# Adafruit_2_4in_TFT_Breakout.net
KiCad netlist of a schematic drawn in EAGLE
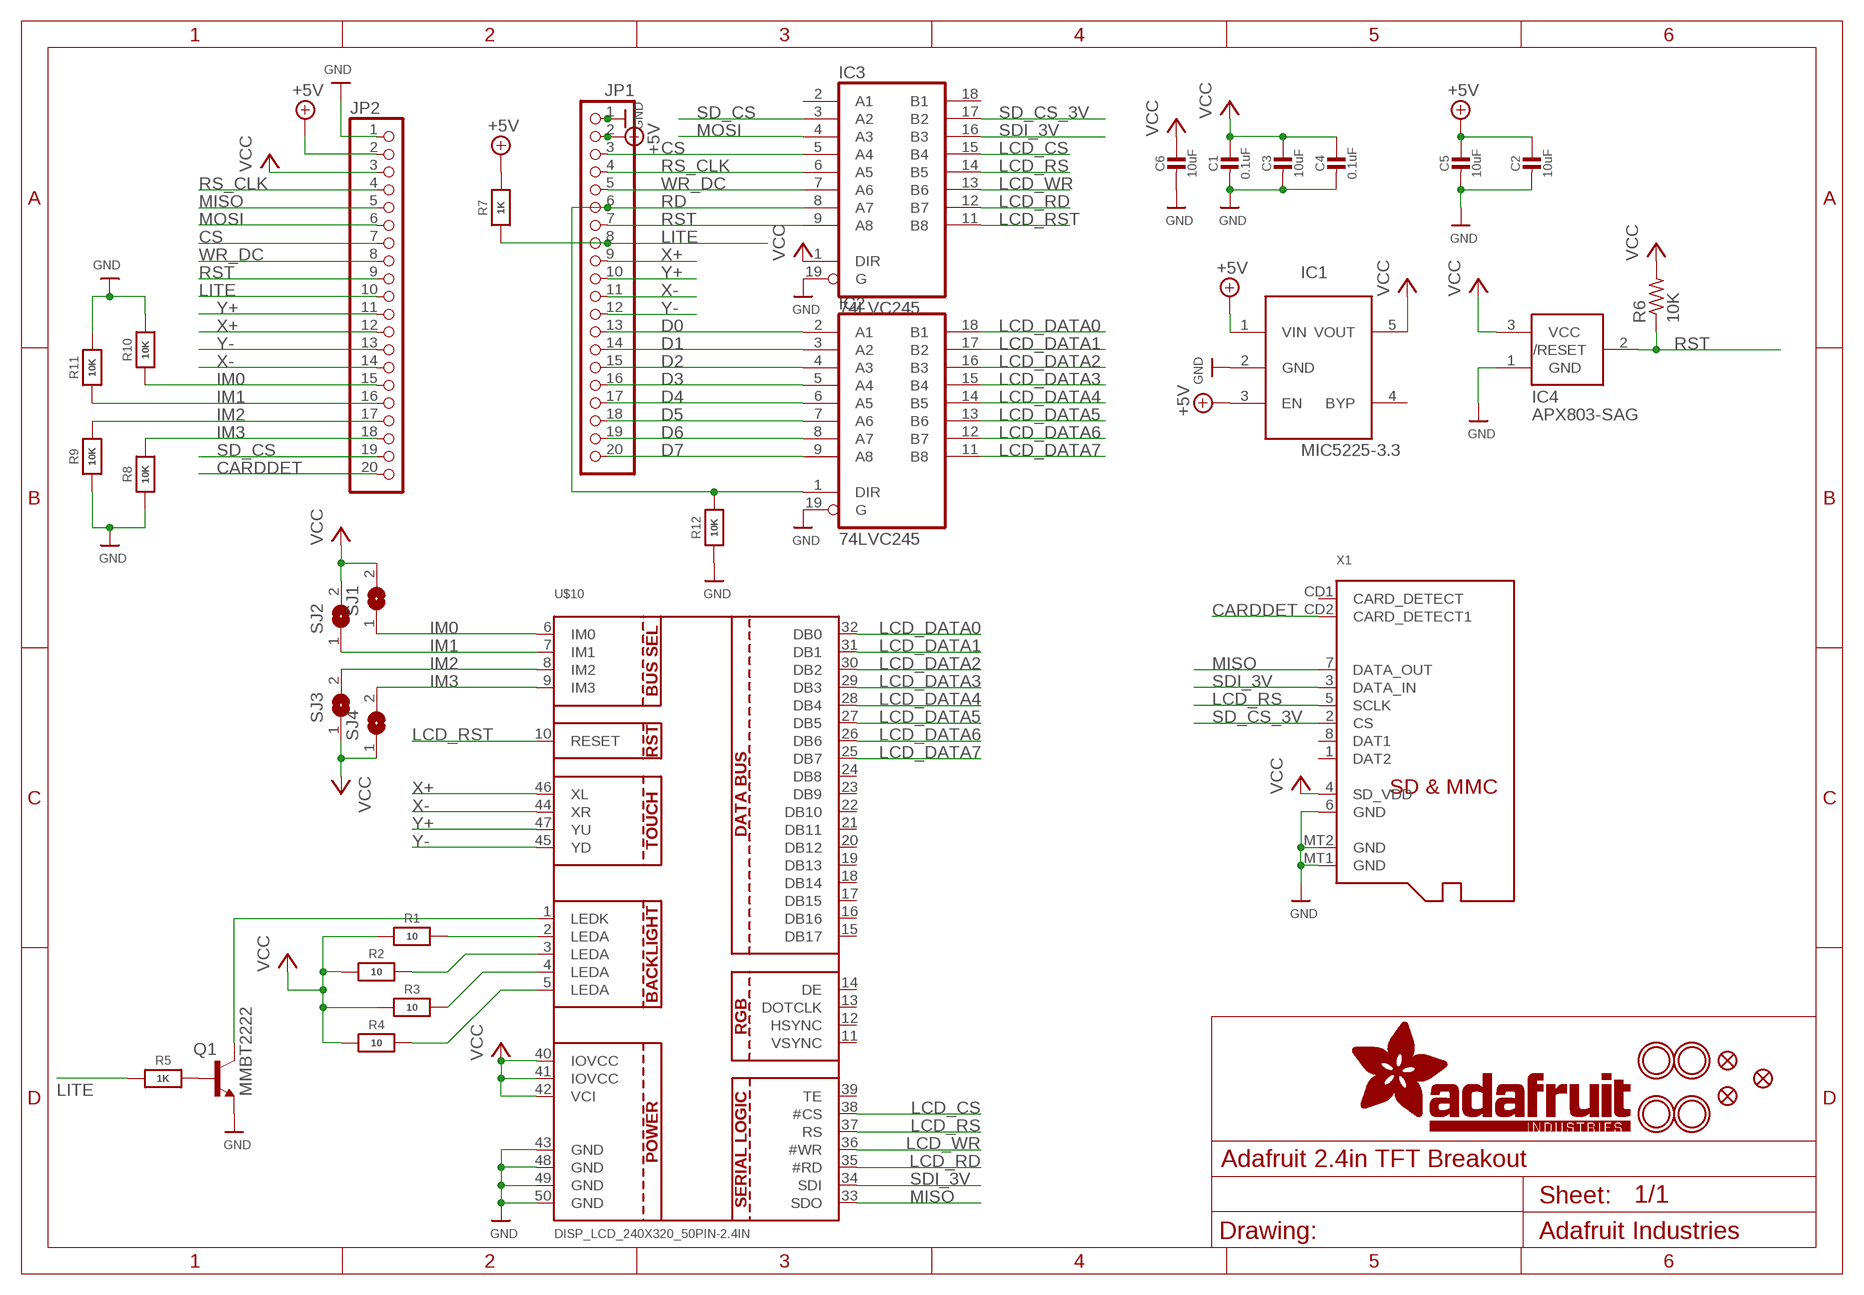
[diagram p0: schematic, sheet 1]

(export (version "E")
  (design (tool "Eeschema 10.0.6"))
  (components
    (comp (ref "C1")
      (value "0.1uF")
      (footprint "eagle-import:0805-NO")
      (libsource (lib "eagle-import") (part "CAP_CERAMIC0805-NOOUTLINE"))
    )
    (comp (ref "C2")
      (value "10uF")
      (footprint "eagle-import:0805-NO")
      (libsource (lib "eagle-import") (part "CAP_CERAMIC0805-NOOUTLINE"))
    )
    (comp (ref "C3")
      (value "10uF")
      (footprint "eagle-import:0805-NO")
      (libsource (lib "eagle-import") (part "CAP_CERAMIC0805-NOOUTLINE"))
    )
    (comp (ref "C4")
      (value "0.1uF")
      (footprint "eagle-import:0805-NO")
      (libsource (lib "eagle-import") (part "CAP_CERAMIC0805-NOOUTLINE"))
    )
    (comp (ref "C5")
      (value "10uF")
      (footprint "eagle-import:0805-NO")
      (libsource (lib "eagle-import") (part "CAP_CERAMIC0805-NOOUTLINE"))
    )
    (comp (ref "C6")
      (value "10uF")
      (footprint "eagle-import:0805-NO")
      (libsource (lib "eagle-import") (part "CAP_CERAMIC0805-NOOUTLINE"))
    )
    (comp (ref "IC1")
      (value "MIC5225-3.3")
      (footprint "eagle-import:SOT23-5L")
      (libsource (lib "eagle-import") (part "LP298XS"))
    )
    (comp (ref "IC2")
      (value "74LVC245")
      (footprint "eagle-import:SO20W")
      (libsource (lib "eagle-import") (part "74245DWACT"))
    )
    (comp (ref "IC3")
      (value "74LVC245")
      (footprint "eagle-import:SO20W")
      (libsource (lib "eagle-import") (part "74245DWACT"))
    )
    (comp (ref "IC4")
      (value "APX803-SAG")
      (footprint "eagle-import:SOT23")
      (libsource (lib "eagle-import") (part "AXP083-SAG"))
    )
    (comp (ref "JP1")
      (value "HEADER-1X20ROUND")
      (footprint "eagle-import:1X20_ROUND")
      (libsource (lib "eagle-import") (part "HEADER-1X20ROUND"))
    )
    (comp (ref "JP2")
      (value "HEADER-1X20ROUND")
      (footprint "eagle-import:1X20_ROUND")
      (libsource (lib "eagle-import") (part "HEADER-1X20ROUND"))
    )
    (comp (ref "Q1")
      (value "MMBT2222")
      (footprint "eagle-import:SOT23-BEC")
      (libsource (lib "eagle-import") (part "-NPN-SOT23-BECMMBT2222ALT1"))
    )
    (comp (ref "R1")
      (value "10")
      (footprint "eagle-import:0805-NO")
      (libsource (lib "eagle-import") (part "RESISTOR0805_NOOUTLINE"))
    )
    (comp (ref "R2")
      (value "10")
      (footprint "eagle-import:0805-NO")
      (libsource (lib "eagle-import") (part "RESISTOR0805_NOOUTLINE"))
    )
    (comp (ref "R3")
      (value "10")
      (footprint "eagle-import:0805-NO")
      (libsource (lib "eagle-import") (part "RESISTOR0805_NOOUTLINE"))
    )
    (comp (ref "R4")
      (value "10")
      (footprint "eagle-import:0805-NO")
      (libsource (lib "eagle-import") (part "RESISTOR0805_NOOUTLINE"))
    )
    (comp (ref "R5")
      (value "1K")
      (footprint "eagle-import:0805-NO")
      (libsource (lib "eagle-import") (part "RESISTOR0805_NOOUTLINE"))
    )
    (comp (ref "R6")
      (value "10K")
      (footprint "eagle-import:R0805")
      (libsource (lib "eagle-import") (part "R-US_R0805"))
    )
    (comp (ref "R7")
      (value "1K")
      (footprint "eagle-import:0805-NO")
      (libsource (lib "eagle-import") (part "RESISTOR0805_NOOUTLINE"))
    )
    (comp (ref "R8")
      (value "10K")
      (footprint "eagle-import:0805-NO")
      (libsource (lib "eagle-import") (part "RESISTOR0805_NOOUTLINE"))
    )
    (comp (ref "R9")
      (value "10K")
      (footprint "eagle-import:0805-NO")
      (libsource (lib "eagle-import") (part "RESISTOR0805_NOOUTLINE"))
    )
    (comp (ref "R10")
      (value "10K")
      (footprint "eagle-import:0805-NO")
      (libsource (lib "eagle-import") (part "RESISTOR0805_NOOUTLINE"))
    )
    (comp (ref "R11")
      (value "10K")
      (footprint "eagle-import:0805-NO")
      (libsource (lib "eagle-import") (part "RESISTOR0805_NOOUTLINE"))
    )
    (comp (ref "R12")
      (value "10K")
      (footprint "eagle-import:0805-NO")
      (libsource (lib "eagle-import") (part "RESISTOR0805_NOOUTLINE"))
    )
    (comp (ref "SJ1")
      (value "SOLDERJUMPER")
      (footprint "eagle-import:SOLDERJUMPER_ARROW_NOPASTE")
      (libsource (lib "eagle-import") (part "SOLDERJUMPER"))
    )
    (comp (ref "SJ2")
      (value "SOLDERJUMPER")
      (footprint "eagle-import:SOLDERJUMPER_ARROW_NOPASTE")
      (libsource (lib "eagle-import") (part "SOLDERJUMPER"))
    )
    (comp (ref "SJ3")
      (value "SOLDERJUMPER")
      (footprint "eagle-import:SOLDERJUMPER_ARROW_NOPASTE")
      (libsource (lib "eagle-import") (part "SOLDERJUMPER"))
    )
    (comp (ref "SJ4")
      (value "SOLDERJUMPER")
      (footprint "eagle-import:SOLDERJUMPER_ARROW_NOPASTE")
      (libsource (lib "eagle-import") (part "SOLDERJUMPER"))
    )
    (comp (ref "U$7")
      (value "MOUNTINGHOLE2.5")
      (footprint "eagle-import:MOUNTINGHOLE_2.5_PLATED")
      (libsource (lib "eagle-import") (part "MOUNTINGHOLE2.5"))
    )
    (comp (ref "U$9")
      (value "FIDUCIAL\"\"")
      (footprint "eagle-import:FIDUCIAL_1MM")
      (libsource (lib "eagle-import") (part "FIDUCIAL{dblquote}{dblquote}"))
    )
    (comp (ref "U$10")
      (value "DISP_LCD_240X320_50PIN-2.4IN")
      (footprint "eagle-import:TFT_2.4IN_240X320_50PIN")
      (libsource (lib "eagle-import") (part "DISP_LCD_240X320_50PIN-2.4IN"))
    )
    (comp (ref "U$11")
      (value "FIDUCIAL\"\"")
      (footprint "eagle-import:FIDUCIAL_1MM")
      (libsource (lib "eagle-import") (part "FIDUCIAL{dblquote}{dblquote}"))
    )
    (comp (ref "U$15")
      (value "MOUNTINGHOLE2.5")
      (footprint "eagle-import:MOUNTINGHOLE_2.5_PLATED")
      (libsource (lib "eagle-import") (part "MOUNTINGHOLE2.5"))
    )
    (comp (ref "U$16")
      (value "MOUNTINGHOLE2.5")
      (footprint "eagle-import:MOUNTINGHOLE_2.5_PLATED")
      (libsource (lib "eagle-import") (part "MOUNTINGHOLE2.5"))
    )
    (comp (ref "U$17")
      (value "MOUNTINGHOLE2.5")
      (footprint "eagle-import:MOUNTINGHOLE_2.5_PLATED")
      (libsource (lib "eagle-import") (part "MOUNTINGHOLE2.5"))
    )
    (comp (ref "U$23")
      (value "FIDUCIAL\"\"")
      (footprint "eagle-import:FIDUCIAL_1MM")
      (libsource (lib "eagle-import") (part "FIDUCIAL{dblquote}{dblquote}"))
    )
    (comp (ref "X1")
      (value "MICROSD")
      (footprint "eagle-import:MICROSD")
      (libsource (lib "eagle-import") (part "MICROSD"))
    )
  )
  (nets
    (net (code "1") (name "+5V") (class "Default")
      (node (ref "C2") (pin "1") (pinfunction "1_1") (pintype "passive"))
      (node (ref "C5") (pin "1") (pinfunction "1_1") (pintype "passive"))
      (node (ref "IC1") (pin "1") (pinfunction "VIN_1") (pintype "bidirectional"))
      (node (ref "IC1") (pin "3") (pinfunction "EN_3") (pintype "bidirectional"))
      (node (ref "JP1") (pin "2") (pinfunction "2_2") (pintype "passive"))
      (node (ref "JP2") (pin "2") (pinfunction "2_2") (pintype "passive"))
      (node (ref "R7") (pin "2") (pinfunction "2_2") (pintype "passive"))
    )
    (net (code "2") (name "/CARDDET") (class "Default")
      (node (ref "JP2") (pin "20") (pinfunction "20_20") (pintype "passive"))
      (node (ref "X1") (pin "CD2") (pinfunction "CARD_DETECT1_CD2") (pintype "passive"))
    )
    (net (code "3") (name "/CS") (class "Default")
      (node (ref "IC3") (pin "5") (pinfunction "A4_5") (pintype "bidirectional"))
      (node (ref "JP1") (pin "3") (pinfunction "3_3") (pintype "passive"))
      (node (ref "JP2") (pin "7") (pinfunction "7_7") (pintype "passive"))
    )
    (net (code "4") (name "/D0") (class "Default")
      (node (ref "IC2") (pin "2") (pinfunction "A1_2") (pintype "bidirectional"))
      (node (ref "JP1") (pin "13") (pinfunction "13_13") (pintype "passive"))
    )
    (net (code "5") (name "/D1") (class "Default")
      (node (ref "IC2") (pin "3") (pinfunction "A2_3") (pintype "bidirectional"))
      (node (ref "JP1") (pin "14") (pinfunction "14_14") (pintype "passive"))
    )
    (net (code "6") (name "/D2") (class "Default")
      (node (ref "IC2") (pin "4") (pinfunction "A3_4") (pintype "bidirectional"))
      (node (ref "JP1") (pin "15") (pinfunction "15_15") (pintype "passive"))
    )
    (net (code "7") (name "/D3") (class "Default")
      (node (ref "IC2") (pin "5") (pinfunction "A4_5") (pintype "bidirectional"))
      (node (ref "JP1") (pin "16") (pinfunction "16_16") (pintype "passive"))
    )
    (net (code "8") (name "/D4") (class "Default")
      (node (ref "IC2") (pin "6") (pinfunction "A5_6") (pintype "bidirectional"))
      (node (ref "JP1") (pin "17") (pinfunction "17_17") (pintype "passive"))
    )
    (net (code "9") (name "/D5") (class "Default")
      (node (ref "IC2") (pin "7") (pinfunction "A6_7") (pintype "bidirectional"))
      (node (ref "JP1") (pin "18") (pinfunction "18_18") (pintype "passive"))
    )
    (net (code "10") (name "/D6") (class "Default")
      (node (ref "IC2") (pin "8") (pinfunction "A7_8") (pintype "bidirectional"))
      (node (ref "JP1") (pin "19") (pinfunction "19_19") (pintype "passive"))
    )
    (net (code "11") (name "/D7") (class "Default")
      (node (ref "IC2") (pin "9") (pinfunction "A8_9") (pintype "bidirectional"))
      (node (ref "JP1") (pin "20") (pinfunction "20_20") (pintype "passive"))
    )
    (net (code "12") (name "/IM0") (class "Default")
      (node (ref "JP2") (pin "15") (pinfunction "15_15") (pintype "passive"))
      (node (ref "R10") (pin "1") (pinfunction "1_1") (pintype "passive"))
      (node (ref "SJ1") (pin "1") (pinfunction "1_1") (pintype "passive"))
      (node (ref "U$10") (pin "6") (pinfunction "IM0_6") (pintype "bidirectional"))
    )
    (net (code "13") (name "/IM1") (class "Default")
      (node (ref "JP2") (pin "16") (pinfunction "16_16") (pintype "passive"))
      (node (ref "R11") (pin "1") (pinfunction "1_1") (pintype "passive"))
      (node (ref "SJ2") (pin "1") (pinfunction "1_1") (pintype "passive"))
      (node (ref "U$10") (pin "7") (pinfunction "IM1_7") (pintype "bidirectional"))
    )
    (net (code "14") (name "/IM2") (class "Default")
      (node (ref "JP2") (pin "17") (pinfunction "17_17") (pintype "passive"))
      (node (ref "R9") (pin "2") (pinfunction "2_2") (pintype "passive"))
      (node (ref "SJ3") (pin "2") (pinfunction "2_2") (pintype "passive"))
      (node (ref "U$10") (pin "8") (pinfunction "IM2_8") (pintype "bidirectional"))
    )
    (net (code "15") (name "/IM3") (class "Default")
      (node (ref "JP2") (pin "18") (pinfunction "18_18") (pintype "passive"))
      (node (ref "R8") (pin "2") (pinfunction "2_2") (pintype "passive"))
      (node (ref "SJ4") (pin "2") (pinfunction "2_2") (pintype "passive"))
      (node (ref "U$10") (pin "9") (pinfunction "IM3_9") (pintype "bidirectional"))
    )
    (net (code "16") (name "/LCD_CS") (class "Default")
      (node (ref "IC3") (pin "15") (pinfunction "B4_15") (pintype "bidirectional"))
      (node (ref "U$10") (pin "38") (pinfunction "#CS_38") (pintype "bidirectional"))
    )
    (net (code "17") (name "/LCD_DATA0") (class "Default")
      (node (ref "IC2") (pin "18") (pinfunction "B1_18") (pintype "bidirectional"))
      (node (ref "U$10") (pin "32") (pinfunction "DB0_32") (pintype "bidirectional"))
    )
    (net (code "18") (name "/LCD_DATA1") (class "Default")
      (node (ref "IC2") (pin "17") (pinfunction "B2_17") (pintype "bidirectional"))
      (node (ref "U$10") (pin "31") (pinfunction "DB1_31") (pintype "bidirectional"))
    )
    (net (code "19") (name "/LCD_DATA2") (class "Default")
      (node (ref "IC2") (pin "16") (pinfunction "B3_16") (pintype "bidirectional"))
      (node (ref "U$10") (pin "30") (pinfunction "DB2_30") (pintype "bidirectional"))
    )
    (net (code "20") (name "/LCD_DATA3") (class "Default")
      (node (ref "IC2") (pin "15") (pinfunction "B4_15") (pintype "bidirectional"))
      (node (ref "U$10") (pin "29") (pinfunction "DB3_29") (pintype "bidirectional"))
    )
    (net (code "21") (name "/LCD_DATA4") (class "Default")
      (node (ref "IC2") (pin "14") (pinfunction "B5_14") (pintype "bidirectional"))
      (node (ref "U$10") (pin "28") (pinfunction "DB4_28") (pintype "bidirectional"))
    )
    (net (code "22") (name "/LCD_DATA5") (class "Default")
      (node (ref "IC2") (pin "13") (pinfunction "B6_13") (pintype "bidirectional"))
      (node (ref "U$10") (pin "27") (pinfunction "DB5_27") (pintype "bidirectional"))
    )
    (net (code "23") (name "/LCD_DATA6") (class "Default")
      (node (ref "IC2") (pin "12") (pinfunction "B7_12") (pintype "bidirectional"))
      (node (ref "U$10") (pin "26") (pinfunction "DB6_26") (pintype "bidirectional"))
    )
    (net (code "24") (name "/LCD_DATA7") (class "Default")
      (node (ref "IC2") (pin "11") (pinfunction "B8_11") (pintype "bidirectional"))
      (node (ref "U$10") (pin "25") (pinfunction "DB7_25") (pintype "bidirectional"))
    )
    (net (code "25") (name "/LCD_RD") (class "Default")
      (node (ref "IC3") (pin "12") (pinfunction "B7_12") (pintype "bidirectional"))
      (node (ref "U$10") (pin "35") (pinfunction "#RD_35") (pintype "bidirectional"))
    )
    (net (code "26") (name "/LCD_RS") (class "Default")
      (node (ref "IC3") (pin "14") (pinfunction "B5_14") (pintype "bidirectional"))
      (node (ref "U$10") (pin "37") (pinfunction "RS_37") (pintype "bidirectional"))
      (node (ref "X1") (pin "5") (pinfunction "SCLK_5") (pintype "input"))
    )
    (net (code "27") (name "/LCD_RST") (class "Default")
      (node (ref "IC3") (pin "11") (pinfunction "B8_11") (pintype "bidirectional"))
      (node (ref "U$10") (pin "10") (pinfunction "RESET_10") (pintype "bidirectional"))
    )
    (net (code "28") (name "/LCD_WR") (class "Default")
      (node (ref "IC3") (pin "13") (pinfunction "B6_13") (pintype "bidirectional"))
      (node (ref "U$10") (pin "36") (pinfunction "#WR_36") (pintype "bidirectional"))
    )
    (net (code "29") (name "/LITE") (class "Default")
      (node (ref "JP1") (pin "8") (pinfunction "8_8") (pintype "passive"))
      (node (ref "JP2") (pin "10") (pinfunction "10_10") (pintype "passive"))
      (node (ref "R5") (pin "1") (pinfunction "1_1") (pintype "passive"))
      (node (ref "R7") (pin "1") (pinfunction "1_1") (pintype "passive"))
    )
    (net (code "30") (name "/MISO") (class "Default")
      (node (ref "JP2") (pin "5") (pinfunction "5_5") (pintype "passive"))
      (node (ref "U$10") (pin "33") (pinfunction "SDO_33") (pintype "bidirectional"))
      (node (ref "X1") (pin "7") (pinfunction "DATA_OUT_7") (pintype "output"))
    )
    (net (code "31") (name "/MOSI") (class "Default")
      (node (ref "IC3") (pin "4") (pinfunction "A3_4") (pintype "bidirectional"))
      (node (ref "JP2") (pin "6") (pinfunction "6_6") (pintype "passive"))
    )
    (net (code "32") (name "/RD") (class "Default")
      (node (ref "IC2") (pin "1") (pinfunction "DIR_1") (pintype "input"))
      (node (ref "IC3") (pin "8") (pinfunction "A7_8") (pintype "bidirectional"))
      (node (ref "JP1") (pin "6") (pinfunction "6_6") (pintype "passive"))
      (node (ref "R12") (pin "2") (pinfunction "2_2") (pintype "passive"))
    )
    (net (code "33") (name "/RST") (class "Default")
      (node (ref "IC3") (pin "9") (pinfunction "A8_9") (pintype "bidirectional"))
      (node (ref "IC4") (pin "2") (pinfunction "/RESET_2") (pintype "output"))
      (node (ref "JP1") (pin "7") (pinfunction "7_7") (pintype "passive"))
      (node (ref "JP2") (pin "9") (pinfunction "9_9") (pintype "passive"))
      (node (ref "R6") (pin "1") (pinfunction "1_1") (pintype "passive"))
    )
    (net (code "34") (name "/RS_CLK") (class "Default")
      (node (ref "IC3") (pin "6") (pinfunction "A5_6") (pintype "bidirectional"))
      (node (ref "JP1") (pin "4") (pinfunction "4_4") (pintype "passive"))
      (node (ref "JP2") (pin "4") (pinfunction "4_4") (pintype "passive"))
    )
    (net (code "35") (name "/SDI_3V") (class "Default")
      (node (ref "IC3") (pin "16") (pinfunction "B3_16") (pintype "bidirectional"))
      (node (ref "U$10") (pin "34") (pinfunction "SDI_34") (pintype "bidirectional"))
      (node (ref "X1") (pin "3") (pinfunction "DATA_IN_3") (pintype "input"))
    )
    (net (code "36") (name "/SD_CS") (class "Default")
      (node (ref "IC3") (pin "3") (pinfunction "A2_3") (pintype "bidirectional"))
      (node (ref "JP2") (pin "19") (pinfunction "19_19") (pintype "passive"))
    )
    (net (code "37") (name "/SD_CS_3V") (class "Default")
      (node (ref "IC3") (pin "17") (pinfunction "B2_17") (pintype "bidirectional"))
      (node (ref "X1") (pin "2") (pinfunction "CS_2") (pintype "input"))
    )
    (net (code "38") (name "/WR_DC") (class "Default")
      (node (ref "IC3") (pin "7") (pinfunction "A6_7") (pintype "bidirectional"))
      (node (ref "JP1") (pin "5") (pinfunction "5_5") (pintype "passive"))
      (node (ref "JP2") (pin "8") (pinfunction "8_8") (pintype "passive"))
    )
    (net (code "39") (name "/X+") (class "Default")
      (node (ref "JP1") (pin "9") (pinfunction "9_9") (pintype "passive"))
      (node (ref "JP2") (pin "12") (pinfunction "12_12") (pintype "passive"))
      (node (ref "U$10") (pin "46") (pinfunction "XL_46") (pintype "bidirectional"))
    )
    (net (code "40") (name "/X-") (class "Default")
      (node (ref "JP1") (pin "11") (pinfunction "11_11") (pintype "passive"))
      (node (ref "JP2") (pin "14") (pinfunction "14_14") (pintype "passive"))
      (node (ref "U$10") (pin "44") (pinfunction "XR_44") (pintype "bidirectional"))
    )
    (net (code "41") (name "/Y+") (class "Default")
      (node (ref "JP1") (pin "10") (pinfunction "10_10") (pintype "passive"))
      (node (ref "JP2") (pin "11") (pinfunction "11_11") (pintype "passive"))
      (node (ref "U$10") (pin "47") (pinfunction "YU_47") (pintype "bidirectional"))
    )
    (net (code "42") (name "/Y-") (class "Default")
      (node (ref "JP1") (pin "12") (pinfunction "12_12") (pintype "passive"))
      (node (ref "JP2") (pin "13") (pinfunction "13_13") (pintype "passive"))
      (node (ref "U$10") (pin "45") (pinfunction "YD_45") (pintype "bidirectional"))
    )
    (net (code "43") (name "GND") (class "Default")
      (node (ref "C1") (pin "2") (pinfunction "2_2") (pintype "passive"))
      (node (ref "C2") (pin "2") (pinfunction "2_2") (pintype "passive"))
      (node (ref "C3") (pin "2") (pinfunction "2_2") (pintype "passive"))
      (node (ref "C4") (pin "2") (pinfunction "2_2") (pintype "passive"))
      (node (ref "C5") (pin "2") (pinfunction "2_2") (pintype "passive"))
      (node (ref "C6") (pin "2") (pinfunction "2_2") (pintype "passive"))
      (node (ref "IC1") (pin "2") (pinfunction "GND_2") (pintype "bidirectional"))
      (node (ref "IC2") (pin "19") (pinfunction "G_19") (pintype "input"))
      (node (ref "IC3") (pin "19") (pinfunction "G_19") (pintype "input"))
      (node (ref "IC4") (pin "1") (pinfunction "GND_1") (pintype "power_in"))
      (node (ref "JP1") (pin "1") (pinfunction "1_1") (pintype "passive"))
      (node (ref "JP2") (pin "1") (pinfunction "1_1") (pintype "passive"))
      (node (ref "Q1") (pin "E") (pinfunction "E_E") (pintype "passive"))
      (node (ref "R10") (pin "2") (pinfunction "2_2") (pintype "passive"))
      (node (ref "R11") (pin "2") (pinfunction "2_2") (pintype "passive"))
      (node (ref "R12") (pin "1") (pinfunction "1_1") (pintype "passive"))
      (node (ref "R8") (pin "1") (pinfunction "1_1") (pintype "passive"))
      (node (ref "R9") (pin "1") (pinfunction "1_1") (pintype "passive"))
      (node (ref "U$10") (pin "43") (pinfunction "GND_43") (pintype "bidirectional"))
      (node (ref "U$10") (pin "48") (pinfunction "GND_48") (pintype "bidirectional"))
      (node (ref "U$10") (pin "49") (pinfunction "GND_49") (pintype "bidirectional"))
      (node (ref "U$10") (pin "50") (pinfunction "GND_50") (pintype "bidirectional"))
      (node (ref "X1") (pin "6") (pinfunction "GND_6") (pintype "power_in"))
      (node (ref "X1") (pin "MT1") (pinfunction "GND_MT1") (pintype "power_in"))
      (node (ref "X1") (pin "MT2") (pinfunction "GND_MT2") (pintype "power_in"))
    )
    (net (code "44") (name "Net-(Q1-PadB)") (class "Default")
      (node (ref "Q1") (pin "B") (pinfunction "B_B") (pintype "passive"))
      (node (ref "R5") (pin "2") (pinfunction "2_2") (pintype "passive"))
    )
    (net (code "45") (name "Net-(R1-Pad2)") (class "Default")
      (node (ref "R1") (pin "2") (pinfunction "2_2") (pintype "passive"))
      (node (ref "U$10") (pin "2") (pinfunction "LEDA_2") (pintype "bidirectional"))
    )
    (net (code "46") (name "Net-(R2-Pad2)") (class "Default")
      (node (ref "R2") (pin "2") (pinfunction "2_2") (pintype "passive"))
      (node (ref "U$10") (pin "3") (pinfunction "LEDA_3") (pintype "bidirectional"))
    )
    (net (code "47") (name "Net-(R3-Pad2)") (class "Default")
      (node (ref "R3") (pin "2") (pinfunction "2_2") (pintype "passive"))
      (node (ref "U$10") (pin "4") (pinfunction "LEDA_4") (pintype "bidirectional"))
    )
    (net (code "48") (name "Net-(R4-Pad2)") (class "Default")
      (node (ref "R4") (pin "2") (pinfunction "2_2") (pintype "passive"))
      (node (ref "U$10") (pin "5") (pinfunction "LEDA_5") (pintype "bidirectional"))
    )
    (net (code "49") (name "Net-(U$10-LEDK)") (class "Default")
      (node (ref "Q1") (pin "C") (pinfunction "C_C") (pintype "passive"))
      (node (ref "U$10") (pin "1") (pinfunction "LEDK_1") (pintype "bidirectional"))
    )
    (net (code "50") (name "VCC") (class "Default")
      (node (ref "C1") (pin "1") (pinfunction "1_1") (pintype "passive"))
      (node (ref "C3") (pin "1") (pinfunction "1_1") (pintype "passive"))
      (node (ref "C4") (pin "1") (pinfunction "1_1") (pintype "passive"))
      (node (ref "C6") (pin "1") (pinfunction "1_1") (pintype "passive"))
      (node (ref "IC1") (pin "5") (pinfunction "VOUT_5") (pintype "bidirectional"))
      (node (ref "IC3") (pin "1") (pinfunction "DIR_1") (pintype "input"))
      (node (ref "IC4") (pin "3") (pinfunction "VCC_3") (pintype "power_in"))
      (node (ref "JP2") (pin "3") (pinfunction "3_3") (pintype "passive"))
      (node (ref "R1") (pin "1") (pinfunction "1_1") (pintype "passive"))
      (node (ref "R2") (pin "1") (pinfunction "1_1") (pintype "passive"))
      (node (ref "R3") (pin "1") (pinfunction "1_1") (pintype "passive"))
      (node (ref "R4") (pin "1") (pinfunction "1_1") (pintype "passive"))
      (node (ref "R6") (pin "2") (pinfunction "2_2") (pintype "passive"))
      (node (ref "SJ1") (pin "2") (pinfunction "2_2") (pintype "passive"))
      (node (ref "SJ2") (pin "2") (pinfunction "2_2") (pintype "passive"))
      (node (ref "SJ3") (pin "1") (pinfunction "1_1") (pintype "passive"))
      (node (ref "SJ4") (pin "1") (pinfunction "1_1") (pintype "passive"))
      (node (ref "U$10") (pin "40") (pinfunction "IOVCC_40") (pintype "bidirectional"))
      (node (ref "U$10") (pin "41") (pinfunction "IOVCC_41") (pintype "bidirectional"))
      (node (ref "U$10") (pin "42") (pinfunction "VCI_42") (pintype "bidirectional"))
      (node (ref "X1") (pin "4") (pinfunction "SD_VDD_4") (pintype "power_in"))
    )
    (net (code "51") (name "unconnected-(IC1-BYP-Pad4)") (class "Default")
      (node (ref "IC1") (pin "4") (pinfunction "BYP_4") (pintype "bidirectional"))
    )
    (net (code "52") (name "unconnected-(IC3A-A1-Pad2)") (class "Default")
      (node (ref "IC3") (pin "2") (pinfunction "A1_2") (pintype "bidirectional"))
    )
    (net (code "53") (name "unconnected-(IC3A-B1-Pad18)") (class "Default")
      (node (ref "IC3") (pin "18") (pinfunction "B1_18") (pintype "bidirectional"))
    )
    (net (code "54") (name "unconnected-(U$10-DB8-Pad24)") (class "Default")
      (node (ref "U$10") (pin "24") (pinfunction "DB8_24") (pintype "bidirectional"))
    )
    (net (code "55") (name "unconnected-(U$10-DB9-Pad23)") (class "Default")
      (node (ref "U$10") (pin "23") (pinfunction "DB9_23") (pintype "bidirectional"))
    )
    (net (code "56") (name "unconnected-(U$10-DB10-Pad22)") (class "Default")
      (node (ref "U$10") (pin "22") (pinfunction "DB10_22") (pintype "bidirectional"))
    )
    (net (code "57") (name "unconnected-(U$10-DB11-Pad21)") (class "Default")
      (node (ref "U$10") (pin "21") (pinfunction "DB11_21") (pintype "bidirectional"))
    )
    (net (code "58") (name "unconnected-(U$10-DB12-Pad20)") (class "Default")
      (node (ref "U$10") (pin "20") (pinfunction "DB12_20") (pintype "bidirectional"))
    )
    (net (code "59") (name "unconnected-(U$10-DB13-Pad19)") (class "Default")
      (node (ref "U$10") (pin "19") (pinfunction "DB13_19") (pintype "bidirectional"))
    )
    (net (code "60") (name "unconnected-(U$10-DB14-Pad18)") (class "Default")
      (node (ref "U$10") (pin "18") (pinfunction "DB14_18") (pintype "bidirectional"))
    )
    (net (code "61") (name "unconnected-(U$10-DB15-Pad17)") (class "Default")
      (node (ref "U$10") (pin "17") (pinfunction "DB15_17") (pintype "bidirectional"))
    )
    (net (code "62") (name "unconnected-(U$10-DB16-Pad16)") (class "Default")
      (node (ref "U$10") (pin "16") (pinfunction "DB16_16") (pintype "bidirectional"))
    )
    (net (code "63") (name "unconnected-(U$10-DB17-Pad15)") (class "Default")
      (node (ref "U$10") (pin "15") (pinfunction "DB17_15") (pintype "bidirectional"))
    )
    (net (code "64") (name "unconnected-(U$10-DE-Pad14)") (class "Default")
      (node (ref "U$10") (pin "14") (pinfunction "DE_14") (pintype "bidirectional"))
    )
    (net (code "65") (name "unconnected-(U$10-DOTCLK-Pad13)") (class "Default")
      (node (ref "U$10") (pin "13") (pinfunction "DOTCLK_13") (pintype "bidirectional"))
    )
    (net (code "66") (name "unconnected-(U$10-HSYNC-Pad12)") (class "Default")
      (node (ref "U$10") (pin "12") (pinfunction "HSYNC_12") (pintype "bidirectional"))
    )
    (net (code "67") (name "unconnected-(U$10-TE-Pad39)") (class "Default")
      (node (ref "U$10") (pin "39") (pinfunction "TE_39") (pintype "bidirectional"))
    )
    (net (code "68") (name "unconnected-(U$10-VSYNC-Pad11)") (class "Default")
      (node (ref "U$10") (pin "11") (pinfunction "VSYNC_11") (pintype "bidirectional"))
    )
    (net (code "69") (name "unconnected-(X1-CARD_DETECT-PadCD1)") (class "Default")
      (node (ref "X1") (pin "CD1") (pinfunction "CARD_DETECT_CD1") (pintype "passive"))
    )
    (net (code "70") (name "unconnected-(X1-DAT1-Pad8)") (class "Default")
      (node (ref "X1") (pin "8") (pinfunction "DAT1_8") (pintype "bidirectional"))
    )
    (net (code "71") (name "unconnected-(X1-DAT2-Pad1)") (class "Default")
      (node (ref "X1") (pin "1") (pinfunction "DAT2_1") (pintype "bidirectional"))
    )
  )
)
